# fetboard.net
KiCad netlist of a schematic drawn in EAGLE
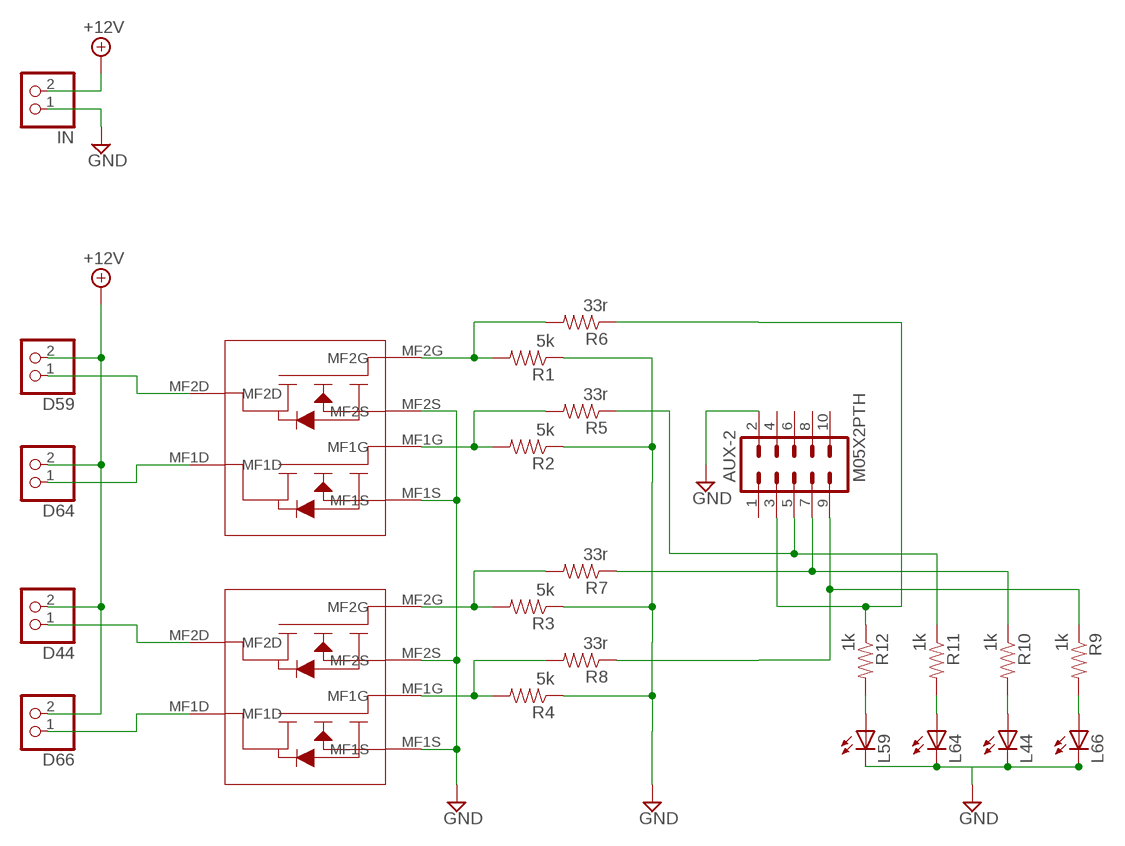
[diagram p0: schematic, sheet 1]

(export (version "E")
  (design (tool "Eeschema 10.0.6"))
  (components
    (comp (ref "AUX-2")
      (value "M05X2PTH")
      (footprint "eagle-import:AVR_ICSP")
      (libsource (lib "eagle-import") (part "M05X2PTH"))
    )
    (comp (ref "D44")
      (value "PINHD-1X2")
      (footprint "eagle-import:1X02")
      (libsource (lib "eagle-import") (part "PINHD-1X2"))
    )
    (comp (ref "D59")
      (value "PINHD-1X2")
      (footprint "eagle-import:1X02")
      (libsource (lib "eagle-import") (part "PINHD-1X2"))
    )
    (comp (ref "D64")
      (value "PINHD-1X2")
      (footprint "eagle-import:1X02")
      (libsource (lib "eagle-import") (part "PINHD-1X2"))
    )
    (comp (ref "D66")
      (value "PINHD-1X2")
      (footprint "eagle-import:1X02")
      (libsource (lib "eagle-import") (part "PINHD-1X2"))
    )
    (comp (ref "FET1")
      (value "IPG20N04S4L-11")
      (footprint "eagle-import:SUPERSO8")
      (libsource (lib "eagle-import") (part "IPG20N04S4L-11"))
    )
    (comp (ref "FET2")
      (value "IPG20N04S4L-11")
      (footprint "eagle-import:SUPERSO8")
      (libsource (lib "eagle-import") (part "IPG20N04S4L-11"))
    )
    (comp (ref "IN")
      (value "PINHD-1X2")
      (footprint "eagle-import:1X02")
      (libsource (lib "eagle-import") (part "PINHD-1X2"))
    )
    (comp (ref "L44")
      (value "LEDCHIPLED_0805")
      (footprint "eagle-import:CHIPLED_0805")
      (libsource (lib "eagle-import") (part "LEDCHIPLED_0805"))
    )
    (comp (ref "L59")
      (value "LEDCHIPLED_0805")
      (footprint "eagle-import:CHIPLED_0805")
      (libsource (lib "eagle-import") (part "LEDCHIPLED_0805"))
    )
    (comp (ref "L64")
      (value "LEDCHIPLED_0805")
      (footprint "eagle-import:CHIPLED_0805")
      (libsource (lib "eagle-import") (part "LEDCHIPLED_0805"))
    )
    (comp (ref "L66")
      (value "LEDCHIPLED_0805")
      (footprint "eagle-import:CHIPLED_0805")
      (libsource (lib "eagle-import") (part "LEDCHIPLED_0805"))
    )
    (comp (ref "R1")
      (value "5k")
      (footprint "eagle-import:0805")
      (libsource (lib "eagle-import") (part "RESISTOR0805-RES"))
    )
    (comp (ref "R2")
      (value "5k")
      (footprint "eagle-import:0805")
      (libsource (lib "eagle-import") (part "RESISTOR0805-RES"))
    )
    (comp (ref "R3")
      (value "5k")
      (footprint "eagle-import:0805")
      (libsource (lib "eagle-import") (part "RESISTOR0805-RES"))
    )
    (comp (ref "R4")
      (value "5k")
      (footprint "eagle-import:0805")
      (libsource (lib "eagle-import") (part "RESISTOR0805-RES"))
    )
    (comp (ref "R5")
      (value "33r")
      (footprint "eagle-import:0805")
      (libsource (lib "eagle-import") (part "RESISTOR0805-RES"))
    )
    (comp (ref "R6")
      (value "33r")
      (footprint "eagle-import:0805")
      (libsource (lib "eagle-import") (part "RESISTOR0805-RES"))
    )
    (comp (ref "R7")
      (value "33r")
      (footprint "eagle-import:0805")
      (libsource (lib "eagle-import") (part "RESISTOR0805-RES"))
    )
    (comp (ref "R8")
      (value "33r")
      (footprint "eagle-import:0805")
      (libsource (lib "eagle-import") (part "RESISTOR0805-RES"))
    )
    (comp (ref "R9")
      (value "1k")
      (footprint "eagle-import:0805")
      (libsource (lib "eagle-import") (part "RESISTOR0805-RES"))
    )
    (comp (ref "R10")
      (value "1k")
      (footprint "eagle-import:0805")
      (libsource (lib "eagle-import") (part "RESISTOR0805-RES"))
    )
    (comp (ref "R11")
      (value "1k")
      (footprint "eagle-import:0805")
      (libsource (lib "eagle-import") (part "RESISTOR0805-RES"))
    )
    (comp (ref "R12")
      (value "1k")
      (footprint "eagle-import:0805")
      (libsource (lib "eagle-import") (part "RESISTOR0805-RES"))
    )
  )
  (nets
    (net (code "1") (name "+12V") (class "Default")
      (node (ref "D44") (pin "2") (pinfunction "2_2") (pintype "passive"))
      (node (ref "D59") (pin "2") (pinfunction "2_2") (pintype "passive"))
      (node (ref "D64") (pin "2") (pinfunction "2_2") (pintype "passive"))
      (node (ref "D66") (pin "2") (pinfunction "2_2") (pintype "passive"))
      (node (ref "IN") (pin "2") (pinfunction "2_2") (pintype "passive"))
    )
    (net (code "2") (name "GND") (class "Default")
      (node (ref "AUX-2") (pin "2") (pinfunction "2_2") (pintype "passive"))
      (node (ref "FET1") (pin "MF1S") (pinfunction "MF1S_MF1S") (pintype "bidirectional"))
      (node (ref "FET1") (pin "MF2S") (pinfunction "MF2S_MF2S") (pintype "bidirectional"))
      (node (ref "FET2") (pin "MF1S") (pinfunction "MF1S_MF1S") (pintype "bidirectional"))
      (node (ref "FET2") (pin "MF2S") (pinfunction "MF2S_MF2S") (pintype "bidirectional"))
      (node (ref "IN") (pin "1") (pinfunction "1_1") (pintype "passive"))
      (node (ref "L44") (pin "C") (pinfunction "C_C") (pintype "passive"))
      (node (ref "L59") (pin "C") (pinfunction "C_C") (pintype "passive"))
      (node (ref "L64") (pin "C") (pinfunction "C_C") (pintype "passive"))
      (node (ref "L66") (pin "C") (pinfunction "C_C") (pintype "passive"))
      (node (ref "R1") (pin "1") (pinfunction "1_1") (pintype "passive"))
      (node (ref "R2") (pin "1") (pinfunction "1_1") (pintype "passive"))
      (node (ref "R3") (pin "1") (pinfunction "1_1") (pintype "passive"))
      (node (ref "R4") (pin "1") (pinfunction "1_1") (pintype "passive"))
    )
    (net (code "3") (name "Net-(AUX-2-Pad3)") (class "Default")
      (node (ref "AUX-2") (pin "3") (pinfunction "3_3") (pintype "passive"))
      (node (ref "R12") (pin "1") (pinfunction "1_1") (pintype "passive"))
      (node (ref "R6") (pin "1") (pinfunction "1_1") (pintype "passive"))
    )
    (net (code "4") (name "Net-(AUX-2-Pad5)") (class "Default")
      (node (ref "AUX-2") (pin "5") (pinfunction "5_5") (pintype "passive"))
      (node (ref "R11") (pin "1") (pinfunction "1_1") (pintype "passive"))
      (node (ref "R5") (pin "1") (pinfunction "1_1") (pintype "passive"))
    )
    (net (code "5") (name "Net-(AUX-2-Pad7)") (class "Default")
      (node (ref "AUX-2") (pin "7") (pinfunction "7_7") (pintype "passive"))
      (node (ref "R10") (pin "1") (pinfunction "1_1") (pintype "passive"))
      (node (ref "R7") (pin "1") (pinfunction "1_1") (pintype "passive"))
    )
    (net (code "6") (name "Net-(AUX-2-Pad9)") (class "Default")
      (node (ref "AUX-2") (pin "9") (pinfunction "9_9") (pintype "passive"))
      (node (ref "R8") (pin "1") (pinfunction "1_1") (pintype "passive"))
      (node (ref "R9") (pin "1") (pinfunction "1_1") (pintype "passive"))
    )
    (net (code "7") (name "Net-(D44-Pad1)") (class "Default")
      (node (ref "D44") (pin "1") (pinfunction "1_1") (pintype "passive"))
      (node (ref "FET2") (pin "MF2D") (pinfunction "MF2D_MF2D") (pintype "bidirectional"))
    )
    (net (code "8") (name "Net-(D59-Pad1)") (class "Default")
      (node (ref "D59") (pin "1") (pinfunction "1_1") (pintype "passive"))
      (node (ref "FET1") (pin "MF2D") (pinfunction "MF2D_MF2D") (pintype "bidirectional"))
    )
    (net (code "9") (name "Net-(D64-Pad1)") (class "Default")
      (node (ref "D64") (pin "1") (pinfunction "1_1") (pintype "passive"))
      (node (ref "FET1") (pin "MF1D") (pinfunction "MF1D_MF1D") (pintype "bidirectional"))
    )
    (net (code "10") (name "Net-(D66-Pad1)") (class "Default")
      (node (ref "D66") (pin "1") (pinfunction "1_1") (pintype "passive"))
      (node (ref "FET2") (pin "MF1D") (pinfunction "MF1D_MF1D") (pintype "bidirectional"))
    )
    (net (code "11") (name "Net-(FET1-PadMF1G)") (class "Default")
      (node (ref "FET1") (pin "MF1G") (pinfunction "MF1G_MF1G") (pintype "bidirectional"))
      (node (ref "R2") (pin "2") (pinfunction "2_2") (pintype "passive"))
      (node (ref "R5") (pin "2") (pinfunction "2_2") (pintype "passive"))
    )
    (net (code "12") (name "Net-(FET1-PadMF2G)") (class "Default")
      (node (ref "FET1") (pin "MF2G") (pinfunction "MF2G_MF2G") (pintype "bidirectional"))
      (node (ref "R1") (pin "2") (pinfunction "2_2") (pintype "passive"))
      (node (ref "R6") (pin "2") (pinfunction "2_2") (pintype "passive"))
    )
    (net (code "13") (name "Net-(FET2-PadMF1G)") (class "Default")
      (node (ref "FET2") (pin "MF1G") (pinfunction "MF1G_MF1G") (pintype "bidirectional"))
      (node (ref "R4") (pin "2") (pinfunction "2_2") (pintype "passive"))
      (node (ref "R8") (pin "2") (pinfunction "2_2") (pintype "passive"))
    )
    (net (code "14") (name "Net-(FET2-PadMF2G)") (class "Default")
      (node (ref "FET2") (pin "MF2G") (pinfunction "MF2G_MF2G") (pintype "bidirectional"))
      (node (ref "R3") (pin "2") (pinfunction "2_2") (pintype "passive"))
      (node (ref "R7") (pin "2") (pinfunction "2_2") (pintype "passive"))
    )
    (net (code "15") (name "Net-(L44-PadA)") (class "Default")
      (node (ref "L44") (pin "A") (pinfunction "A_A") (pintype "passive"))
      (node (ref "R10") (pin "2") (pinfunction "2_2") (pintype "passive"))
    )
    (net (code "16") (name "Net-(L59-PadA)") (class "Default")
      (node (ref "L59") (pin "A") (pinfunction "A_A") (pintype "passive"))
      (node (ref "R12") (pin "2") (pinfunction "2_2") (pintype "passive"))
    )
    (net (code "17") (name "Net-(L64-PadA)") (class "Default")
      (node (ref "L64") (pin "A") (pinfunction "A_A") (pintype "passive"))
      (node (ref "R11") (pin "2") (pinfunction "2_2") (pintype "passive"))
    )
    (net (code "18") (name "Net-(L66-PadA)") (class "Default")
      (node (ref "L66") (pin "A") (pinfunction "A_A") (pintype "passive"))
      (node (ref "R9") (pin "2") (pinfunction "2_2") (pintype "passive"))
    )
    (net (code "19") (name "unconnected-(AUX-2-Pad1)") (class "Default")
      (node (ref "AUX-2") (pin "1") (pinfunction "1_1") (pintype "passive"))
    )
    (net (code "20") (name "unconnected-(AUX-2-Pad4)") (class "Default")
      (node (ref "AUX-2") (pin "4") (pinfunction "4_4") (pintype "passive"))
    )
    (net (code "21") (name "unconnected-(AUX-2-Pad6)") (class "Default")
      (node (ref "AUX-2") (pin "6") (pinfunction "6_6") (pintype "passive"))
    )
    (net (code "22") (name "unconnected-(AUX-2-Pad8)") (class "Default")
      (node (ref "AUX-2") (pin "8") (pinfunction "8_8") (pintype "passive"))
    )
    (net (code "23") (name "unconnected-(AUX-2-Pad10)") (class "Default")
      (node (ref "AUX-2") (pin "10") (pinfunction "10_10") (pintype "passive"))
    )
  )
)
